# imu.net
KiCad netlist of a schematic drawn in Altium Designer
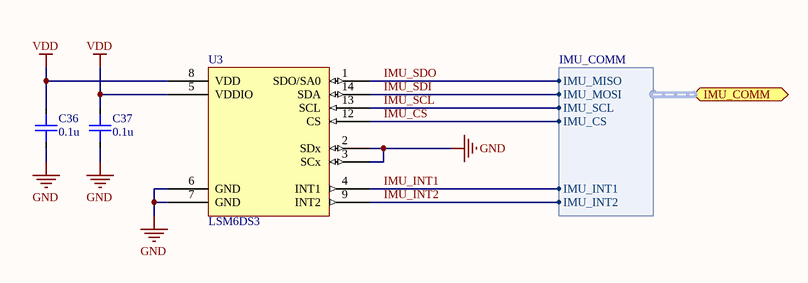
[diagram p0: imu.SchDoc]

(export (version "E")
  (design (tool "Eeschema 10.0.6"))
  (components
    (comp (ref "C36")
      (value "0.1u")
      (footprint "C0402")
      (description "Capacitor")
      (libsource (lib "misc") (part "Capacitor"))
    )
    (comp (ref "C37")
      (value "0.1u")
      (footprint "C0402")
      (description "Capacitor")
      (libsource (lib "misc") (part "Capacitor"))
    )
    (comp (ref "U3")
      (value "LSM6DS3")
      (footprint "LSM6DS3")
      (description "IC - Inertial Measurement Unit, Accelerometer, Gyroscope, 6D")
      (libsource (lib "ecg-go") (part "LSM6DS3"))
    )
  )
  (nets
    (net (code "2") (name "/IMU_CS") (class "Default")
      (node (ref "U3") (pin "12") (pinfunction "CS_12") (pintype "input"))
    )
    (net (code "3") (name "/IMU_INT1") (class "Default")
      (node (ref "U3") (pin "4") (pinfunction "INT1_4") (pintype "output"))
    )
    (net (code "4") (name "/IMU_INT2") (class "Default")
      (node (ref "U3") (pin "9") (pinfunction "INT2_9") (pintype "output"))
    )
    (net (code "5") (name "/IMU_SCL") (class "Default")
      (node (ref "U3") (pin "13") (pinfunction "SCL_13") (pintype "input"))
    )
    (net (code "6") (name "/IMU_SDI") (class "Default")
      (node (ref "U3") (pin "14") (pinfunction "SDA_14") (pintype "bidirectional"))
    )
    (net (code "7") (name "/IMU_SDO") (class "Default")
      (node (ref "U3") (pin "1") (pinfunction "SDO/SA0_1") (pintype "bidirectional"))
    )
    (net (code "9") (name "GND") (class "Default")
      (node (ref "C36") (pin "1") (pinfunction "1_1") (pintype "passive"))
      (node (ref "C37") (pin "1") (pinfunction "1_1") (pintype "passive"))
      (node (ref "U3") (pin "2") (pinfunction "SDx_2") (pintype "bidirectional"))
      (node (ref "U3") (pin "3") (pinfunction "SCx_3") (pintype "bidirectional"))
      (node (ref "U3") (pin "6") (pinfunction "GND_6") (pintype "power_in"))
      (node (ref "U3") (pin "7") (pinfunction "GND_7") (pintype "power_in"))
    )
    (net (code "10") (name "VDD") (class "Default")
      (node (ref "C36") (pin "2") (pinfunction "2_2") (pintype "passive"))
      (node (ref "C37") (pin "2") (pinfunction "2_2") (pintype "passive"))
      (node (ref "U3") (pin "5") (pinfunction "VDDIO_5") (pintype "power_in"))
      (node (ref "U3") (pin "8") (pinfunction "VDD_8") (pintype "power_in"))
    )
  )
)
